# load.net
KiCad netlist of a schematic drawn in EAGLE
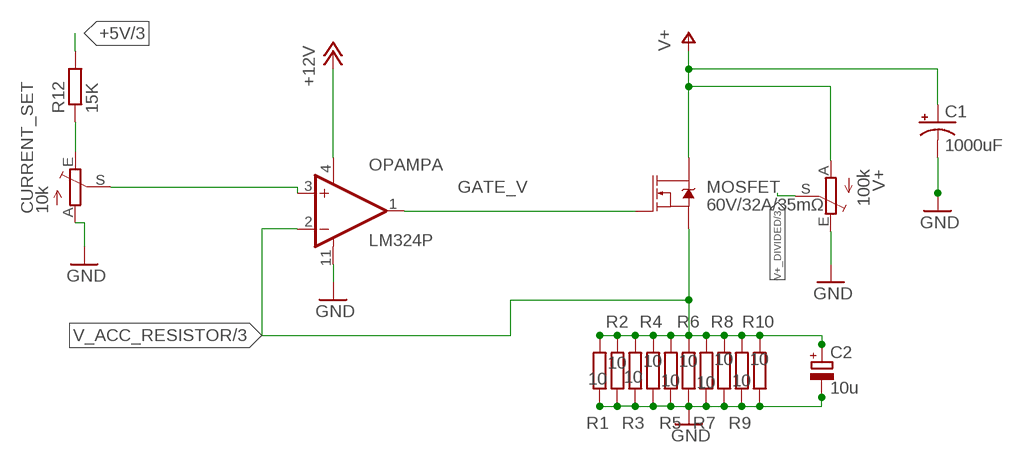
[diagram p0: schematic, sheet 1]
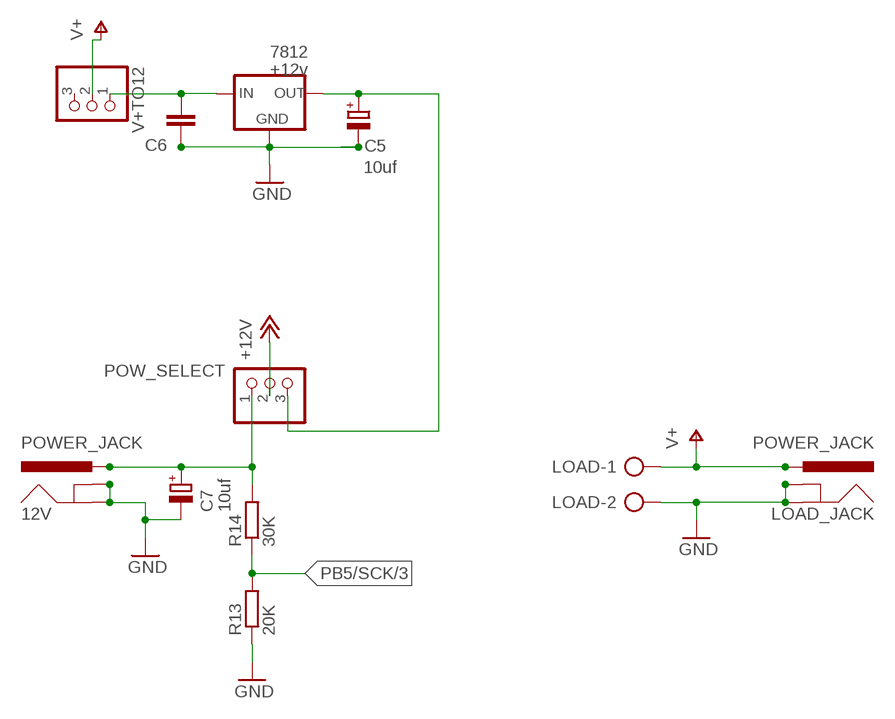
[diagram p1: schematic, sheet 2]
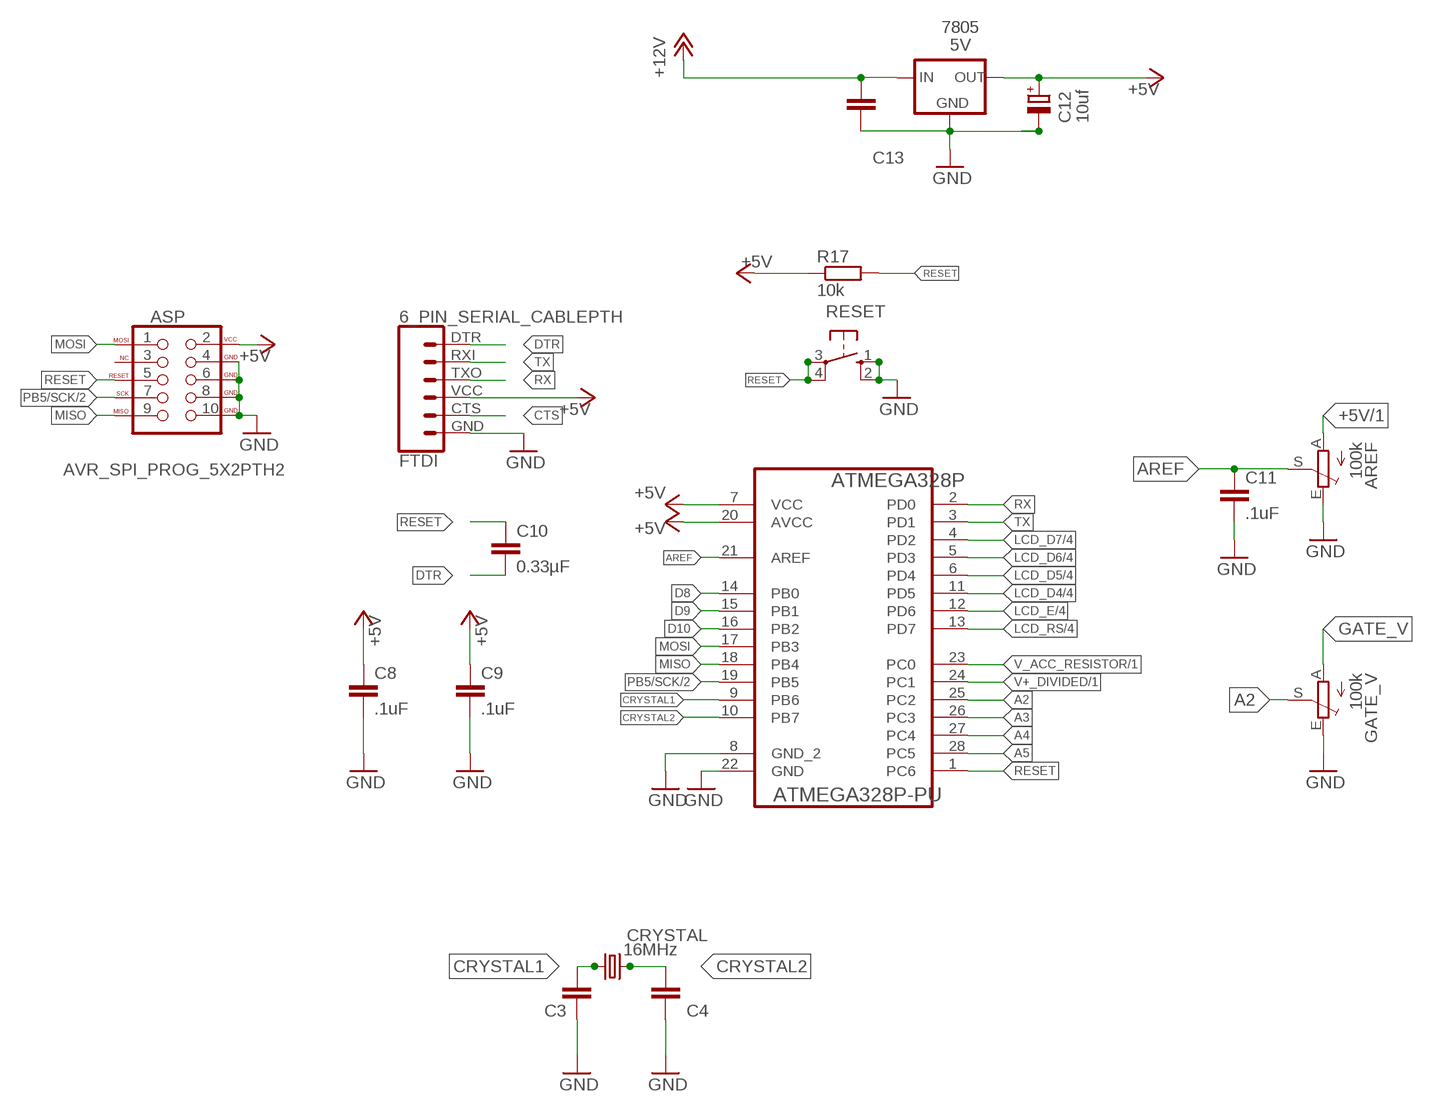
[diagram p2: schematic, sheet 3]
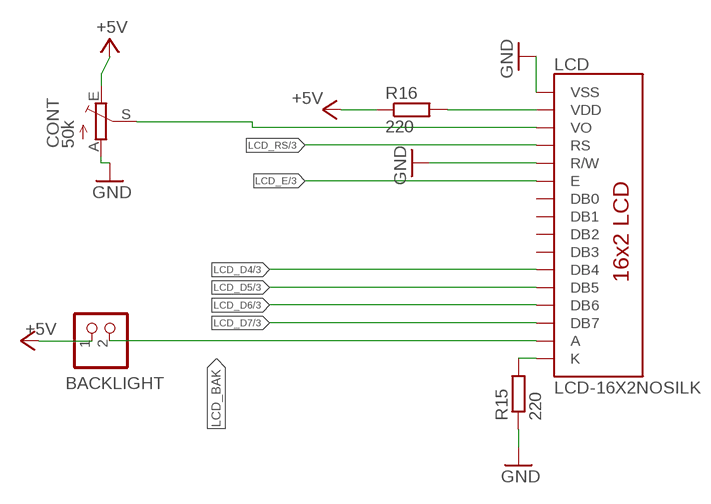
[diagram p3: schematic, sheet 4]

(export (version "E")
  (design (tool "Eeschema 10.0.6"))
  (components
    (comp (ref "7805")
      (value "5V")
      (footprint "eagle-import:TO-252")
      (libsource (lib "eagle-import") (part "V_REG_78XX7812"))
    )
    (comp (ref "AREF")
      (value "100k")
      (footprint "eagle-import:S64W")
      (libsource (lib "eagle-import") (part "TRIM_EU-S64W"))
    )
    (comp (ref "ASP")
      (value "AVR_SPI_PROG_5X2PTH2")
      (footprint "eagle-import:2X5-SHROUDED")
      (libsource (lib "eagle-import") (part "AVR_SPI_PROG_5X2PTH2"))
    )
    (comp (ref "ATMEGA328P")
      (value "ATMEGA328P-PU")
      (footprint "eagle-import:DIP254P762X457-28")
      (libsource (lib "eagle-import") (part "ATMEGA328P-PU"))
    )
    (comp (ref "C3")
      (value "22pF")
      (footprint "eagle-import:C0805K")
      (libsource (lib "eagle-import") (part "C-EUC0805K"))
    )
    (comp (ref "C4")
      (value "22pF")
      (footprint "eagle-import:C0805K")
      (libsource (lib "eagle-import") (part "C-EUC0805K"))
    )
    (comp (ref "C8")
      (value ".1uF")
      (footprint "eagle-import:C0805K")
      (libsource (lib "eagle-import") (part "C-EUC0805K"))
    )
    (comp (ref "C9")
      (value ".1uF")
      (footprint "eagle-import:C0805K")
      (libsource (lib "eagle-import") (part "C-EUC0805K"))
    )
    (comp (ref "C10")
      (value "0.33µF")
      (footprint "eagle-import:C0805K")
      (libsource (lib "eagle-import") (part "C-EUC0805K"))
    )
    (comp (ref "C11")
      (value ".1uF")
      (footprint "eagle-import:C0805K")
      (libsource (lib "eagle-import") (part "C-EUC0805K"))
    )
    (comp (ref "C12")
      (value "10uf")
      (footprint "eagle-import:E2,5-6")
      (libsource (lib "eagle-import") (part "resistor_CPOL-EUE2.5-6"))
    )
    (comp (ref "C13")
      (value ".1uf")
      (footprint "eagle-import:C0805K")
      (libsource (lib "eagle-import") (part "C-EUC0805K"))
    )
    (comp (ref "CRYSTAL")
      (value "16MHz")
      (footprint "eagle-import:HC49U70")
      (libsource (lib "eagle-import") (part "CRYSTALHC49U70"))
    )
    (comp (ref "FTDI")
      (value "6_PIN_SERIAL_CABLEPTH")
      (footprint "eagle-import:FTDI_BASIC")
      (libsource (lib "eagle-import") (part "6_PIN_SERIAL_CABLEPTH"))
    )
    (comp (ref "GATE_V")
      (value "100k")
      (footprint "eagle-import:S64W")
      (libsource (lib "eagle-import") (part "TRIM_EU-S64W"))
    )
    (comp (ref "R17")
      (value "10k")
      (footprint "eagle-import:M0805")
      (libsource (lib "eagle-import") (part "resistor_348_R-EU_M0805"))
    )
    (comp (ref "RESET")
      (value "10-XX")
      (footprint "eagle-import:B3F-10XX")
      (fields (field (name "MPN") "B3F-1000"))
      (libsource (lib "eagle-import") (part "10-XX"))
    )
    (comp (ref "12V")
      (value "POWER_JACK")
      (footprint "eagle-import:POWER_JACK_PTH")
      (libsource (lib "eagle-import") (part "POWER_JACK"))
    )
    (comp (ref "7812")
      (value "+12v")
      (footprint "eagle-import:TO-252")
      (libsource (lib "eagle-import") (part "V_REG_78XX7812"))
    )
    (comp (ref "C5")
      (value "10uf")
      (footprint "eagle-import:E2,5-6")
      (libsource (lib "eagle-import") (part "resistor_CPOL-EUE2.5-6"))
    )
    (comp (ref "C6")
      (value ".1uF")
      (footprint "eagle-import:C0805K")
      (libsource (lib "eagle-import") (part "C-EUC0805K"))
    )
    (comp (ref "C7")
      (value "10uf")
      (footprint "eagle-import:E2,5-6")
      (libsource (lib "eagle-import") (part "resistor_CPOL-EUE2.5-6"))
    )
    (comp (ref "LOAD")
      (value "AK500/2-H")
      (footprint "eagle-import:AK500_2-H")
      (libsource (lib "eagle-import") (part "AK500/2-H"))
    )
    (comp (ref "LOAD_JACK")
      (value "POWER_JACK")
      (footprint "eagle-import:POWER_JACK_PTH")
      (libsource (lib "eagle-import") (part "POWER_JACK"))
    )
    (comp (ref "POW_SELECT")
      (value "PINHD-1X3")
      (footprint "eagle-import:1X03")
      (libsource (lib "eagle-import") (part "PINHD-1X3"))
    )
    (comp (ref "R13")
      (value "20K")
      (footprint "eagle-import:M0805")
      (libsource (lib "eagle-import") (part "resistor_348_R-EU_M0805"))
    )
    (comp (ref "R14")
      (value "30K")
      (footprint "eagle-import:M0805")
      (libsource (lib "eagle-import") (part "resistor_348_R-EU_M0805"))
    )
    (comp (ref "V+TO12")
      (value "PINHD-1X3")
      (footprint "eagle-import:1X03")
      (libsource (lib "eagle-import") (part "pinhead_325_PINHD-1X3"))
    )
    (comp (ref "C1")
      (value "1000uF")
      (footprint "eagle-import:CPOL-RADIAL-5MM-10MM")
      (libsource (lib "eagle-import") (part "1000UF-RADIAL-5MM-25V-20%"))
    )
    (comp (ref "C2")
      (value "10u")
      (footprint "eagle-import:E2,5-6E")
      (libsource (lib "eagle-import") (part "CPOL-EUE2,5-6E"))
    )
    (comp (ref "CURRENT_SET")
      (value "10k")
      (footprint "eagle-import:S64W")
      (libsource (lib "eagle-import") (part "TRIM_EU-S64W"))
    )
    (comp (ref "MOSFET")
      (value "60V/32A/35mΩ")
      (footprint "eagle-import:TO220V")
      (libsource (lib "eagle-import") (part "MOSFET-NCH-FQP30N06L"))
    )
    (comp (ref "OPAMP")
      (value "LM324P")
      (footprint "eagle-import:DIL14")
      (libsource (lib "eagle-import") (part "LM324P"))
    )
    (comp (ref "R1")
      (value "10")
      (footprint "eagle-import:0207_12")
      (libsource (lib "eagle-import") (part "R-EU_0207/12"))
    )
    (comp (ref "R2")
      (value "10")
      (footprint "eagle-import:0207_12")
      (libsource (lib "eagle-import") (part "R-EU_0207/12"))
    )
    (comp (ref "R3")
      (value "10")
      (footprint "eagle-import:0207_12")
      (libsource (lib "eagle-import") (part "R-EU_0207/12"))
    )
    (comp (ref "R4")
      (value "10")
      (footprint "eagle-import:0207_12")
      (libsource (lib "eagle-import") (part "R-EU_0207/12"))
    )
    (comp (ref "R5")
      (value "10")
      (footprint "eagle-import:0207_12")
      (libsource (lib "eagle-import") (part "R-EU_0207/12"))
    )
    (comp (ref "R6")
      (value "10")
      (footprint "eagle-import:0207_12")
      (libsource (lib "eagle-import") (part "R-EU_0207/12"))
    )
    (comp (ref "R7")
      (value "10")
      (footprint "eagle-import:0207_12")
      (libsource (lib "eagle-import") (part "R-EU_0207/12"))
    )
    (comp (ref "R8")
      (value "10")
      (footprint "eagle-import:0207_12")
      (libsource (lib "eagle-import") (part "R-EU_0207/12"))
    )
    (comp (ref "R9")
      (value "10")
      (footprint "eagle-import:0207_12")
      (libsource (lib "eagle-import") (part "R-EU_0207/12"))
    )
    (comp (ref "R10")
      (value "10")
      (footprint "eagle-import:0207_12")
      (libsource (lib "eagle-import") (part "R-EU_0207/12"))
    )
    (comp (ref "R12")
      (value "15K")
      (footprint "eagle-import:M0805")
      (libsource (lib "eagle-import") (part "resistor_348_R-EU_M0805"))
    )
    (comp (ref "V+")
      (value "100k")
      (footprint "eagle-import:S64W")
      (libsource (lib "eagle-import") (part "TRIM_EU-S64W"))
    )
    (comp (ref "BACKLIGHT")
      (value "PINHD-1X2")
      (footprint "eagle-import:1X02")
      (libsource (lib "eagle-import") (part "PINHD-1X2"))
    )
    (comp (ref "CONT")
      (value "50k")
      (footprint "eagle-import:S64W")
      (libsource (lib "eagle-import") (part "TRIM_EU-S64W"))
    )
    (comp (ref "LCD")
      (value "LCD-16X2NOSILK")
      (footprint "eagle-import:LCD-16X2_NOSILK")
      (libsource (lib "eagle-import") (part "LCD-16X2NOSILK"))
    )
    (comp (ref "R15")
      (value "220")
      (footprint "eagle-import:M0805")
      (libsource (lib "eagle-import") (part "resistor_348_R-EU_M0805"))
    )
    (comp (ref "R16")
      (value "220")
      (footprint "eagle-import:M0805")
      (libsource (lib "eagle-import") (part "resistor_348_R-EU_M0805"))
    )
  )
  (nets
    (net (code "1") (name "+5V") (class "Default")
      (node (ref "7805") (pin "2") (pinfunction "OUT_2") (pintype "passive"))
      (node (ref "AREF") (pin "A") (pinfunction "A_A") (pintype "passive"))
      (node (ref "ASP") (pin "2") (pinfunction "VCC_2") (pintype "power_in"))
      (node (ref "ATMEGA328P") (pin "20") (pinfunction "AVCC_20") (pintype "power_in"))
      (node (ref "ATMEGA328P") (pin "7") (pinfunction "VCC_7") (pintype "power_in"))
      (node (ref "BACKLIGHT") (pin "1") (pinfunction "1_1") (pintype "passive"))
      (node (ref "C12") (pin "+") (pinfunction "+_+") (pintype "passive"))
      (node (ref "C8") (pin "1") (pinfunction "1_1") (pintype "passive"))
      (node (ref "C9") (pin "1") (pinfunction "1_1") (pintype "passive"))
      (node (ref "CONT") (pin "E") (pinfunction "E_E") (pintype "passive"))
      (node (ref "FTDI") (pin "VCC") (pinfunction "4_VCC") (pintype "passive"))
      (node (ref "R12") (pin "2") (pinfunction "2_2") (pintype "passive"))
      (node (ref "R16") (pin "1") (pinfunction "1_1") (pintype "passive"))
      (node (ref "R17") (pin "1") (pinfunction "1_1") (pintype "passive"))
    )
    (net (code "2") (name "+12V") (class "Default")
      (node (ref "7805") (pin "1") (pinfunction "IN_1") (pintype "input"))
      (node (ref "C13") (pin "1") (pinfunction "1_1") (pintype "passive"))
      (node (ref "OPAMP") (pin "4") (pinfunction "V+_4") (pintype "power_in"))
      (node (ref "POW_SELECT") (pin "2") (pinfunction "2_2") (pintype "passive"))
    )
    (net (code "3") (name "A2") (class "Default")
      (node (ref "ATMEGA328P") (pin "25") (pinfunction "PC2_25") (pintype "bidirectional"))
      (node (ref "GATE_V") (pin "S") (pinfunction "S_S") (pintype "passive"))
    )
    (net (code "4") (name "A3") (class "Default")
      (node (ref "ATMEGA328P") (pin "26") (pinfunction "PC3_26") (pintype "bidirectional"))
    )
    (net (code "5") (name "A4") (class "Default")
      (node (ref "ATMEGA328P") (pin "27") (pinfunction "PC4_27") (pintype "bidirectional"))
    )
    (net (code "6") (name "A5") (class "Default")
      (node (ref "ATMEGA328P") (pin "28") (pinfunction "PC5_28") (pintype "bidirectional"))
    )
    (net (code "7") (name "AREF") (class "Default")
      (node (ref "AREF") (pin "S") (pinfunction "S_S") (pintype "passive"))
      (node (ref "ATMEGA328P") (pin "21") (pinfunction "AREF_21") (pintype "input"))
      (node (ref "C11") (pin "1") (pinfunction "1_1") (pintype "passive"))
    )
    (net (code "8") (name "CRYSTAL1") (class "Default")
      (node (ref "ATMEGA328P") (pin "9") (pinfunction "PB6_9") (pintype "bidirectional"))
      (node (ref "C3") (pin "2") (pinfunction "2_2") (pintype "passive"))
      (node (ref "CRYSTAL") (pin "1") (pinfunction "1_1") (pintype "passive"))
    )
    (net (code "9") (name "CRYSTAL2") (class "Default")
      (node (ref "ATMEGA328P") (pin "10") (pinfunction "PB7_10") (pintype "bidirectional"))
      (node (ref "C4") (pin "2") (pinfunction "2_2") (pintype "passive"))
      (node (ref "CRYSTAL") (pin "2") (pinfunction "2_2") (pintype "passive"))
    )
    (net (code "10") (name "CTS") (class "Default")
      (node (ref "FTDI") (pin "CTS") (pinfunction "5_CTS") (pintype "passive"))
    )
    (net (code "11") (name "D8") (class "Default")
      (node (ref "ATMEGA328P") (pin "14") (pinfunction "PB0_14") (pintype "bidirectional"))
    )
    (net (code "12") (name "D9") (class "Default")
      (node (ref "ATMEGA328P") (pin "15") (pinfunction "PB1_15") (pintype "bidirectional"))
    )
    (net (code "13") (name "D10") (class "Default")
      (node (ref "ATMEGA328P") (pin "16") (pinfunction "PB2_16") (pintype "bidirectional"))
    )
    (net (code "14") (name "DTR") (class "Default")
      (node (ref "C10") (pin "2") (pinfunction "2_2") (pintype "passive"))
      (node (ref "FTDI") (pin "DTR") (pinfunction "1_DTR") (pintype "passive"))
    )
    (net (code "15") (name "GATE_V") (class "Default")
      (node (ref "GATE_V") (pin "A") (pinfunction "A_A") (pintype "passive"))
      (node (ref "MOSFET") (pin "1") (pinfunction "G_1") (pintype "bidirectional"))
      (node (ref "OPAMP") (pin "1") (pinfunction "OUT_1") (pintype "output"))
    )
    (net (code "16") (name "GND") (class "Default")
      (node (ref "12V") (pin "GND") (pinfunction "GND_GND") (pintype "bidirectional"))
      (node (ref "12V") (pin "GNDBREAK") (pinfunction "GNDBREAK_GNDBREAK") (pintype "bidirectional"))
      (node (ref "7805") (pin "3") (pinfunction "GND_3") (pintype "input"))
      (node (ref "7812") (pin "3") (pinfunction "GND_3") (pintype "input"))
      (node (ref "AREF") (pin "E") (pinfunction "E_E") (pintype "passive"))
      (node (ref "ASP") (pin "10") (pinfunction "GND_10") (pintype "power_in"))
      (node (ref "ASP") (pin "4") (pinfunction "GND_4") (pintype "power_in"))
      (node (ref "ASP") (pin "6") (pinfunction "GND_6") (pintype "power_in"))
      (node (ref "ASP") (pin "8") (pinfunction "GND_8") (pintype "power_in"))
      (node (ref "ATMEGA328P") (pin "22") (pinfunction "GND_22") (pintype "passive"))
      (node (ref "ATMEGA328P") (pin "8") (pinfunction "GND_2_8") (pintype "passive"))
      (node (ref "C1") (pin "-") (pinfunction "-_-") (pintype "passive"))
      (node (ref "C11") (pin "2") (pinfunction "2_2") (pintype "passive"))
      (node (ref "C12") (pin "-") (pinfunction "-_-") (pintype "passive"))
      (node (ref "C13") (pin "2") (pinfunction "2_2") (pintype "passive"))
      (node (ref "C2") (pin "-") (pinfunction "-_-") (pintype "passive"))
      (node (ref "C3") (pin "1") (pinfunction "1_1") (pintype "passive"))
      (node (ref "C4") (pin "1") (pinfunction "1_1") (pintype "passive"))
      (node (ref "C5") (pin "-") (pinfunction "-_-") (pintype "passive"))
      (node (ref "C6") (pin "2") (pinfunction "2_2") (pintype "passive"))
      (node (ref "C7") (pin "-") (pinfunction "-_-") (pintype "passive"))
      (node (ref "C8") (pin "2") (pinfunction "2_2") (pintype "passive"))
      (node (ref "C9") (pin "2") (pinfunction "2_2") (pintype "passive"))
      (node (ref "CONT") (pin "A") (pinfunction "A_A") (pintype "passive"))
      (node (ref "CURRENT_SET") (pin "A") (pinfunction "A_A") (pintype "passive"))
      (node (ref "FTDI") (pin "GND") (pinfunction "6_GND") (pintype "passive"))
      (node (ref "GATE_V") (pin "E") (pinfunction "E_E") (pintype "passive"))
      (node (ref "LCD") (pin "1") (pinfunction "VSS_1") (pintype "power_in"))
      (node (ref "LCD") (pin "5") (pinfunction "R/W_5") (pintype "input"))
      (node (ref "LOAD") (pin "2") (pinfunction "KL_2") (pintype "passive"))
      (node (ref "LOAD_JACK") (pin "GND") (pinfunction "GND_GND") (pintype "bidirectional"))
      (node (ref "LOAD_JACK") (pin "GNDBREAK") (pinfunction "GNDBREAK_GNDBREAK") (pintype "bidirectional"))
      (node (ref "OPAMP") (pin "11") (pinfunction "V-_11") (pintype "power_in"))
      (node (ref "R1") (pin "1") (pinfunction "1_1") (pintype "passive"))
      (node (ref "R10") (pin "1") (pinfunction "1_1") (pintype "passive"))
      (node (ref "R13") (pin "1") (pinfunction "1_1") (pintype "passive"))
      (node (ref "R15") (pin "1") (pinfunction "1_1") (pintype "passive"))
      (node (ref "R2") (pin "1") (pinfunction "1_1") (pintype "passive"))
      (node (ref "R3") (pin "1") (pinfunction "1_1") (pintype "passive"))
      (node (ref "R4") (pin "1") (pinfunction "1_1") (pintype "passive"))
      (node (ref "R5") (pin "1") (pinfunction "1_1") (pintype "passive"))
      (node (ref "R6") (pin "1") (pinfunction "1_1") (pintype "passive"))
      (node (ref "R7") (pin "1") (pinfunction "1_1") (pintype "passive"))
      (node (ref "R8") (pin "1") (pinfunction "1_1") (pintype "passive"))
      (node (ref "R9") (pin "1") (pinfunction "1_1") (pintype "passive"))
      (node (ref "RESET") (pin "1") (pinfunction "S_1") (pintype "passive"))
      (node (ref "RESET") (pin "2") (pinfunction "S1_2") (pintype "passive"))
      (node (ref "V+") (pin "E") (pinfunction "E_E") (pintype "passive"))
    )
    (net (code "17") (name "LCD_BAK") (class "Default")
      (node (ref "BACKLIGHT") (pin "2") (pinfunction "2_2") (pintype "passive"))
      (node (ref "LCD") (pin "15") (pinfunction "A_15") (pintype "power_in"))
    )
    (net (code "18") (name "LCD_D4") (class "Default")
      (node (ref "ATMEGA328P") (pin "11") (pinfunction "PD5_11") (pintype "bidirectional"))
      (node (ref "LCD") (pin "11") (pinfunction "DB4_11") (pintype "bidirectional"))
    )
    (net (code "19") (name "LCD_D5") (class "Default")
      (node (ref "ATMEGA328P") (pin "6") (pinfunction "PD4_6") (pintype "bidirectional"))
      (node (ref "LCD") (pin "12") (pinfunction "DB5_12") (pintype "bidirectional"))
    )
    (net (code "20") (name "LCD_D6") (class "Default")
      (node (ref "ATMEGA328P") (pin "5") (pinfunction "PD3_5") (pintype "bidirectional"))
      (node (ref "LCD") (pin "13") (pinfunction "DB6_13") (pintype "bidirectional"))
    )
    (net (code "21") (name "LCD_D7") (class "Default")
      (node (ref "ATMEGA328P") (pin "4") (pinfunction "PD2_4") (pintype "bidirectional"))
      (node (ref "LCD") (pin "14") (pinfunction "DB7_14") (pintype "bidirectional"))
    )
    (net (code "22") (name "LCD_E") (class "Default")
      (node (ref "ATMEGA328P") (pin "12") (pinfunction "PD6_12") (pintype "bidirectional"))
      (node (ref "LCD") (pin "6") (pinfunction "E_6") (pintype "input"))
    )
    (net (code "23") (name "LCD_RS") (class "Default")
      (node (ref "ATMEGA328P") (pin "13") (pinfunction "PD7_13") (pintype "bidirectional"))
      (node (ref "LCD") (pin "4") (pinfunction "RS_4") (pintype "input"))
    )
    (net (code "24") (name "MISO") (class "Default")
      (node (ref "ASP") (pin "9") (pinfunction "MISO_9") (pintype "passive"))
      (node (ref "ATMEGA328P") (pin "18") (pinfunction "PB4_18") (pintype "bidirectional"))
    )
    (net (code "25") (name "MOSI") (class "Default")
      (node (ref "ASP") (pin "1") (pinfunction "MOSI_1") (pintype "passive"))
      (node (ref "ATMEGA328P") (pin "17") (pinfunction "PB3_17") (pintype "bidirectional"))
    )
    (net (code "26") (name "Net-(12V-PadPWR)") (class "Default")
      (node (ref "12V") (pin "PWR") (pinfunction "PWR_PWR") (pintype "bidirectional"))
      (node (ref "C7") (pin "+") (pinfunction "+_+") (pintype "passive"))
      (node (ref "POW_SELECT") (pin "1") (pinfunction "1_1") (pintype "passive"))
      (node (ref "R14") (pin "2") (pinfunction "2_2") (pintype "passive"))
    )
    (net (code "27") (name "Net-(7812-IN)") (class "Default")
      (node (ref "7812") (pin "1") (pinfunction "IN_1") (pintype "input"))
      (node (ref "C6") (pin "1") (pinfunction "1_1") (pintype "passive"))
      (node (ref "V+TO12") (pin "1") (pinfunction "1_1") (pintype "passive"))
    )
    (net (code "28") (name "Net-(7812-OUT)") (class "Default")
      (node (ref "7812") (pin "2") (pinfunction "OUT_2") (pintype "passive"))
      (node (ref "C5") (pin "+") (pinfunction "+_+") (pintype "passive"))
      (node (ref "POW_SELECT") (pin "3") (pinfunction "3_3") (pintype "passive"))
    )
    (net (code "29") (name "Net-(CURRENT_SET-PadE)") (class "Default")
      (node (ref "CURRENT_SET") (pin "E") (pinfunction "E_E") (pintype "passive"))
      (node (ref "R12") (pin "1") (pinfunction "1_1") (pintype "passive"))
    )
    (net (code "30") (name "Net-(LCD-K)") (class "Default")
      (node (ref "LCD") (pin "16") (pinfunction "K_16") (pintype "power_in"))
      (node (ref "R15") (pin "2") (pinfunction "2_2") (pintype "passive"))
    )
    (net (code "31") (name "Net-(LCD-VDD)") (class "Default")
      (node (ref "LCD") (pin "2") (pinfunction "VDD_2") (pintype "power_in"))
      (node (ref "R16") (pin "2") (pinfunction "2_2") (pintype "passive"))
    )
    (net (code "32") (name "Net-(LCD-VO)") (class "Default")
      (node (ref "CONT") (pin "S") (pinfunction "S_S") (pintype "passive"))
      (node (ref "LCD") (pin "3") (pinfunction "VO_3") (pintype "bidirectional"))
    )
    (net (code "33") (name "Net-(OPAMPA-+IN)") (class "Default")
      (node (ref "CURRENT_SET") (pin "S") (pinfunction "S_S") (pintype "passive"))
      (node (ref "OPAMP") (pin "3") (pinfunction "+IN_3") (pintype "input"))
    )
    (net (code "34") (name "PB5{slash}SCK") (class "Default")
      (node (ref "ASP") (pin "7") (pinfunction "SCK_7") (pintype "passive"))
      (node (ref "ATMEGA328P") (pin "19") (pinfunction "PB5_19") (pintype "bidirectional"))
      (node (ref "R13") (pin "2") (pinfunction "2_2") (pintype "passive"))
      (node (ref "R14") (pin "1") (pinfunction "1_1") (pintype "passive"))
    )
    (net (code "35") (name "RESET") (class "Default")
      (node (ref "ASP") (pin "5") (pinfunction "RESET_5") (pintype "passive"))
      (node (ref "ATMEGA328P") (pin "1") (pinfunction "PC6_1") (pintype "bidirectional"))
      (node (ref "C10") (pin "1") (pinfunction "1_1") (pintype "passive"))
      (node (ref "R17") (pin "2") (pinfunction "2_2") (pintype "passive"))
      (node (ref "RESET") (pin "3") (pinfunction "P_3") (pintype "passive"))
      (node (ref "RESET") (pin "4") (pinfunction "P1_4") (pintype "passive"))
    )
    (net (code "36") (name "RX") (class "Default")
      (node (ref "ATMEGA328P") (pin "2") (pinfunction "PD0_2") (pintype "bidirectional"))
      (node (ref "FTDI") (pin "TXO") (pinfunction "3_TXO") (pintype "passive"))
    )
    (net (code "37") (name "TX") (class "Default")
      (node (ref "ATMEGA328P") (pin "3") (pinfunction "PD1_3") (pintype "bidirectional"))
      (node (ref "FTDI") (pin "RXI") (pinfunction "2_RXI") (pintype "passive"))
    )
    (net (code "38") (name "V+") (class "Default")
      (node (ref "C1") (pin "+") (pinfunction "+_+") (pintype "passive"))
      (node (ref "LOAD") (pin "1") (pinfunction "KL_1") (pintype "passive"))
      (node (ref "LOAD_JACK") (pin "PWR") (pinfunction "PWR_PWR") (pintype "bidirectional"))
      (node (ref "MOSFET") (pin "2") (pinfunction "D_2") (pintype "bidirectional"))
      (node (ref "V+") (pin "A") (pinfunction "A_A") (pintype "passive"))
      (node (ref "V+TO12") (pin "2") (pinfunction "2_2") (pintype "passive"))
    )
    (net (code "39") (name "V+_DIVIDED") (class "Default")
      (node (ref "ATMEGA328P") (pin "24") (pinfunction "PC1_24") (pintype "bidirectional"))
      (node (ref "V+") (pin "S") (pinfunction "S_S") (pintype "passive"))
    )
    (net (code "40") (name "V_ACC_RESISTOR") (class "Default")
      (node (ref "ATMEGA328P") (pin "23") (pinfunction "PC0_23") (pintype "bidirectional"))
      (node (ref "C2") (pin "+") (pinfunction "+_+") (pintype "passive"))
      (node (ref "MOSFET") (pin "3") (pinfunction "S_3") (pintype "bidirectional"))
      (node (ref "OPAMP") (pin "2") (pinfunction "-IN_2") (pintype "input"))
      (node (ref "R1") (pin "2") (pinfunction "2_2") (pintype "passive"))
      (node (ref "R10") (pin "2") (pinfunction "2_2") (pintype "passive"))
      (node (ref "R2") (pin "2") (pinfunction "2_2") (pintype "passive"))
      (node (ref "R3") (pin "2") (pinfunction "2_2") (pintype "passive"))
      (node (ref "R4") (pin "2") (pinfunction "2_2") (pintype "passive"))
      (node (ref "R5") (pin "2") (pinfunction "2_2") (pintype "passive"))
      (node (ref "R6") (pin "2") (pinfunction "2_2") (pintype "passive"))
      (node (ref "R7") (pin "2") (pinfunction "2_2") (pintype "passive"))
      (node (ref "R8") (pin "2") (pinfunction "2_2") (pintype "passive"))
      (node (ref "R9") (pin "2") (pinfunction "2_2") (pintype "passive"))
    )
    (net (code "41") (name "unconnected-(ASP-NC-Pad3)") (class "Default")
      (node (ref "ASP") (pin "3") (pinfunction "NC_3") (pintype "no_connect"))
    )
    (net (code "42") (name "unconnected-(LCD-DB0-Pad7)") (class "Default")
      (node (ref "LCD") (pin "7") (pinfunction "DB0_7") (pintype "bidirectional"))
    )
    (net (code "43") (name "unconnected-(LCD-DB1-Pad8)") (class "Default")
      (node (ref "LCD") (pin "8") (pinfunction "DB1_8") (pintype "bidirectional"))
    )
    (net (code "44") (name "unconnected-(LCD-DB2-Pad9)") (class "Default")
      (node (ref "LCD") (pin "9") (pinfunction "DB2_9") (pintype "bidirectional"))
    )
    (net (code "45") (name "unconnected-(LCD-DB3-Pad10)") (class "Default")
      (node (ref "LCD") (pin "10") (pinfunction "DB3_10") (pintype "bidirectional"))
    )
    (net (code "46") (name "unconnected-(V+TO12-Pad3)") (class "Default")
      (node (ref "V+TO12") (pin "3") (pinfunction "3_3") (pintype "passive"))
    )
  )
)
